# 11_LCD.net
KiCad netlist of a schematic drawn in Altium Designer
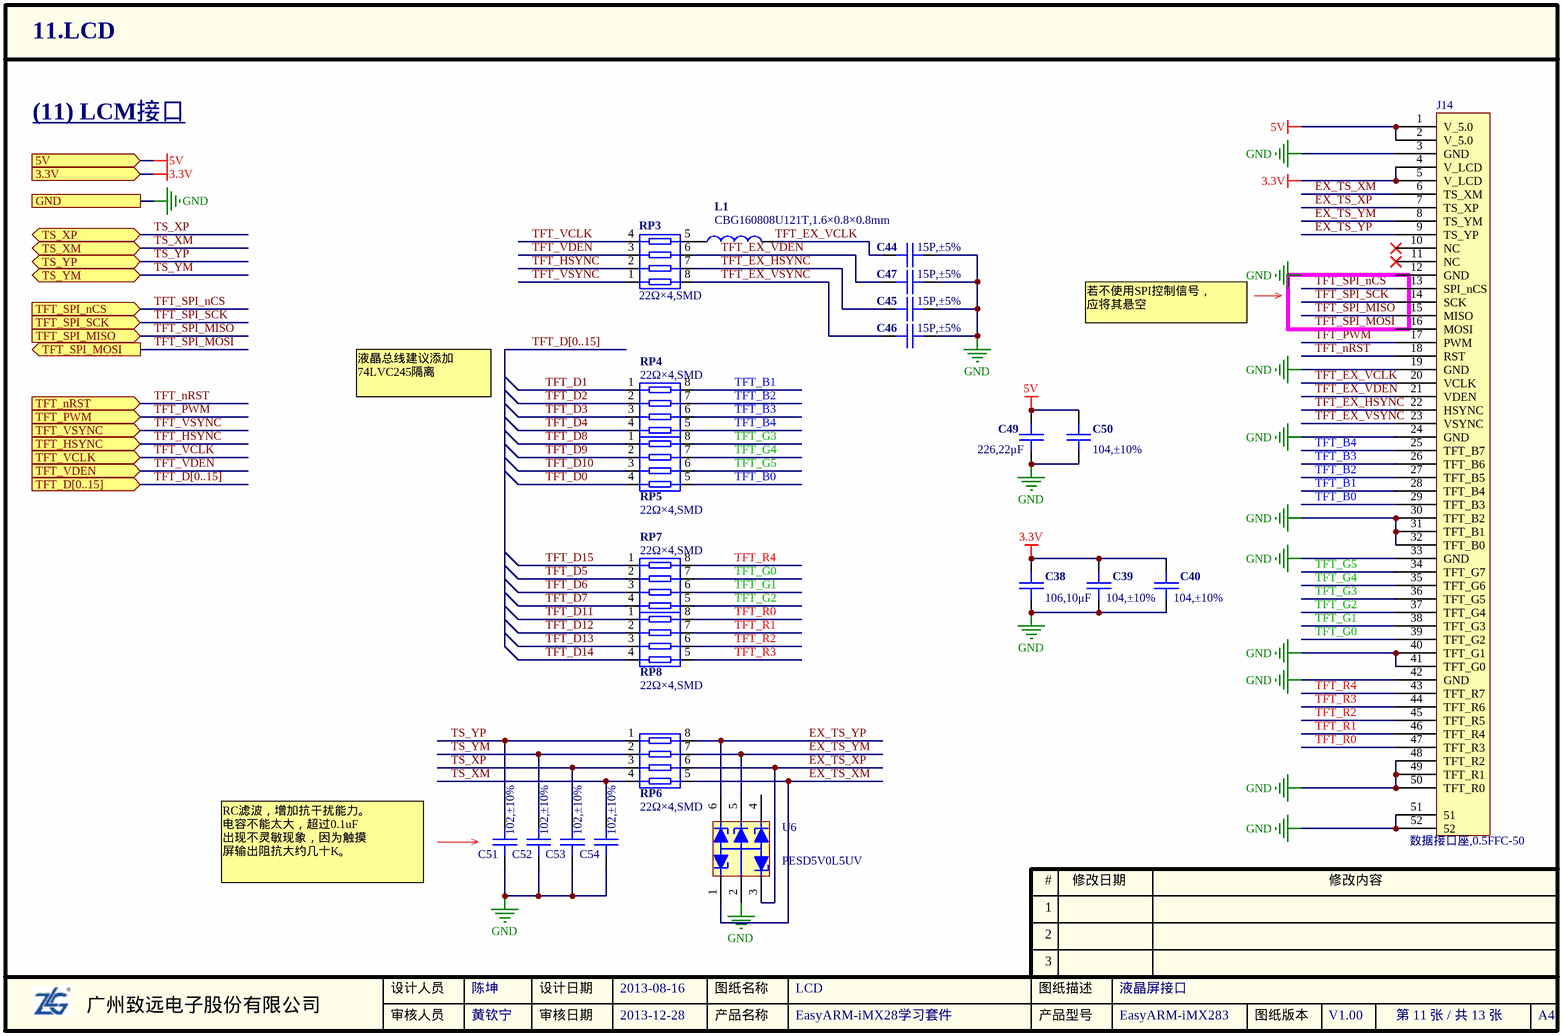
[diagram p0: 11. LCD.SchDoc]

(export (version "E")
  (design (tool "Eeschema 10.0.6"))
  (components
    (comp (ref "C38")
      (value "106,10μF")
      (footprint "0805C")
      (description "106,10μF,±10%,10V,X5R,0805,RoHS")
      (libsource (lib "ErpMaterialData") (part "CAP1"))
    )
    (comp (ref "C39")
      (value "104,±10%")
      (footprint "0603C")
      (description "104,±10%,50V,X7R,0603,*,RoHS")
      (libsource (lib "ErpMaterialData") (part "CAP1"))
    )
    (comp (ref "C40")
      (value "104,±10%")
      (footprint "0603C")
      (description "104,±10%,50V,X7R,0603,*,RoHS")
      (libsource (lib "ErpMaterialData") (part "CAP1"))
    )
    (comp (ref "C44")
      (value "15P,±5%")
      (footprint "0603C")
      (description "15P,±5%,50V,COG,0603,*,RoHS")
      (libsource (lib "ErpMaterialData") (part "CAP1"))
    )
    (comp (ref "C45")
      (value "15P,±5%")
      (footprint "0603C")
      (description "15P,±5%,50V,COG,0603,*,RoHS")
      (libsource (lib "ErpMaterialData") (part "CAP1"))
    )
    (comp (ref "C46")
      (value "15P,±5%")
      (footprint "0603C")
      (description "15P,±5%,50V,COG,0603,*,RoHS")
      (libsource (lib "ErpMaterialData") (part "CAP1"))
    )
    (comp (ref "C47")
      (value "15P,±5%")
      (footprint "0603C")
      (description "15P,±5%,50V,COG,0603,*,RoHS")
      (libsource (lib "ErpMaterialData") (part "CAP1"))
    )
    (comp (ref "C49")
      (value "226,22μF")
      (footprint "0805C")
      (description "226,22μF,±20%,6.3V,X5R,0805,RoHS")
      (libsource (lib "ErpMaterialData") (part "CAP1"))
    )
    (comp (ref "C50")
      (value "104,±10%")
      (footprint "0603C")
      (description "104,±10%,50V,X7R,0603,*,RoHS")
      (libsource (lib "ErpMaterialData") (part "CAP1"))
    )
    (comp (ref "C51")
      (value "102,±10%")
      (footprint "0603C")
      (description "102,±10%,50V,X7R,0603,*,RoHS")
      (libsource (lib "ErpMaterialData") (part "CAP1"))
    )
    (comp (ref "C52")
      (value "102,±10%")
      (footprint "0603C")
      (description "102,±10%,50V,X7R,0603,*,RoHS")
      (libsource (lib "ErpMaterialData") (part "CAP1"))
    )
    (comp (ref "C53")
      (value "102,±10%")
      (footprint "0603C")
      (description "102,±10%,50V,X7R,0603,*,RoHS")
      (libsource (lib "ErpMaterialData") (part "CAP1"))
    )
    (comp (ref "C54")
      (value "102,±10%")
      (footprint "0603C")
      (description "102,±10%,50V,X7R,0603,*,RoHS")
      (libsource (lib "ErpMaterialData") (part "CAP1"))
    )
    (comp (ref "J14")
      (value "数据接口座,0.5FFC-50")
      (footprint "FFC0.5-50P-A")
      (description "数据接口座,0.5FFC-50,SMD,下接,RoHS")
      (fields (field (name "Comment") "FPC-50"))
      (libsource (lib "ErpMaterialData") (part "FPC-50"))
    )
    (comp (ref "L1")
      (value "CBG160808U121T,1.6×0.8×0.8mm")
      (footprint "0603R")
      (description "CBG160808U121T,1.6×0.8×0.8mm,0603,RoHS")
      (fields (field (name "Comment") "INDUCTOR1"))
      (libsource (lib "ErpMaterialData") (part "INDUCTOR1"))
    )
    (comp (ref "RP3")
      (value "22Ω×4,SMD")
      (footprint "0603RA")
      (libsource (lib "ErpMaterialData") (part "RES-P4"))
    )
    (comp (ref "RP4")
      (value "22Ω×4,SMD")
      (footprint "0603RA")
      (libsource (lib "ErpMaterialData") (part "RES-P4"))
    )
    (comp (ref "RP5")
      (value "22Ω×4,SMD")
      (footprint "0603RA")
      (libsource (lib "ErpMaterialData") (part "RES-P4"))
    )
    (comp (ref "RP6")
      (value "22Ω×4,SMD")
      (footprint "0603RA")
      (libsource (lib "ErpMaterialData") (part "RES-P4"))
    )
    (comp (ref "RP7")
      (value "22Ω×4,SMD")
      (footprint "0603RA")
      (libsource (lib "ErpMaterialData") (part "RES-P4"))
    )
    (comp (ref "RP8")
      (value "22Ω×4,SMD")
      (footprint "0603RA")
      (libsource (lib "ErpMaterialData") (part "RES-P4"))
    )
    (comp (ref "U6")
      (value "PESD5V0L5UV")
      (footprint "SOT-666")
      (description "PESD5V0L5UV,SOT-666,NXP,RoHS")
      (libsource (lib "ErpMaterialData") (part "PESD5V0L5UV"))
    )
  )
  (nets
    (net (code "1") (name "/EX_TS_XM") (class "Default")
      (node (ref "J14") (pin "6") (pinfunction "TS_XM_6") (pintype "passive"))
      (node (ref "RP6") (pin "5") (pinfunction "5_5") (pintype "passive"))
      (node (ref "U6") (pin "1") (pintype "passive"))
    )
    (net (code "2") (name "/EX_TS_XP") (class "Default")
      (node (ref "J14") (pin "7") (pinfunction "TS_XP_7") (pintype "passive"))
      (node (ref "RP6") (pin "6") (pinfunction "6_6") (pintype "passive"))
      (node (ref "U6") (pin "3") (pintype "passive"))
    )
    (net (code "3") (name "/EX_TS_YM") (class "Default")
      (node (ref "J14") (pin "8") (pinfunction "TS_YM_8") (pintype "passive"))
      (node (ref "RP6") (pin "7") (pinfunction "7_7") (pintype "passive"))
      (node (ref "U6") (pin "5") (pintype "passive"))
    )
    (net (code "4") (name "/EX_TS_YP") (class "Default")
      (node (ref "J14") (pin "9") (pinfunction "TS_YP_9") (pintype "passive"))
      (node (ref "RP6") (pin "8") (pinfunction "8_8") (pintype "passive"))
      (node (ref "U6") (pin "6") (pintype "passive"))
    )
    (net (code "5") (name "/TFT_B0") (class "Default")
      (node (ref "J14") (pin "29") (pinfunction "TFT_B3_29") (pintype "passive"))
      (node (ref "RP5") (pin "5") (pinfunction "5_5") (pintype "passive"))
    )
    (net (code "6") (name "/TFT_B1") (class "Default")
      (node (ref "J14") (pin "28") (pinfunction "TFT_B4_28") (pintype "passive"))
      (node (ref "RP4") (pin "8") (pinfunction "8_8") (pintype "passive"))
    )
    (net (code "7") (name "/TFT_B2") (class "Default")
      (node (ref "J14") (pin "27") (pinfunction "TFT_B5_27") (pintype "passive"))
      (node (ref "RP4") (pin "7") (pinfunction "7_7") (pintype "passive"))
    )
    (net (code "8") (name "/TFT_B3") (class "Default")
      (node (ref "J14") (pin "26") (pinfunction "TFT_B6_26") (pintype "passive"))
      (node (ref "RP4") (pin "6") (pinfunction "6_6") (pintype "passive"))
    )
    (net (code "9") (name "/TFT_B4") (class "Default")
      (node (ref "J14") (pin "25") (pinfunction "TFT_B7_25") (pintype "passive"))
      (node (ref "RP4") (pin "5") (pinfunction "5_5") (pintype "passive"))
    )
    (net (code "10") (name "/TFT_D0") (class "Default")
      (node (ref "RP5") (pin "4") (pinfunction "4_4") (pintype "passive"))
    )
    (net (code "11") (name "/TFT_D1") (class "Default")
      (node (ref "RP4") (pin "1") (pinfunction "1_1") (pintype "passive"))
    )
    (net (code "12") (name "/TFT_D2") (class "Default")
      (node (ref "RP4") (pin "2") (pinfunction "2_2") (pintype "passive"))
    )
    (net (code "13") (name "/TFT_D3") (class "Default")
      (node (ref "RP4") (pin "3") (pinfunction "3_3") (pintype "passive"))
    )
    (net (code "14") (name "/TFT_D4") (class "Default")
      (node (ref "RP4") (pin "4") (pinfunction "4_4") (pintype "passive"))
    )
    (net (code "15") (name "/TFT_D5") (class "Default")
      (node (ref "RP7") (pin "2") (pinfunction "2_2") (pintype "passive"))
    )
    (net (code "16") (name "/TFT_D6") (class "Default")
      (node (ref "RP7") (pin "3") (pinfunction "3_3") (pintype "passive"))
    )
    (net (code "17") (name "/TFT_D7") (class "Default")
      (node (ref "RP7") (pin "4") (pinfunction "4_4") (pintype "passive"))
    )
    (net (code "18") (name "/TFT_D8") (class "Default")
      (node (ref "RP5") (pin "1") (pinfunction "1_1") (pintype "passive"))
    )
    (net (code "19") (name "/TFT_D9") (class "Default")
      (node (ref "RP5") (pin "2") (pinfunction "2_2") (pintype "passive"))
    )
    (net (code "20") (name "/TFT_D10") (class "Default")
      (node (ref "RP5") (pin "3") (pinfunction "3_3") (pintype "passive"))
    )
    (net (code "21") (name "/TFT_D11") (class "Default")
      (node (ref "RP8") (pin "1") (pinfunction "1_1") (pintype "passive"))
    )
    (net (code "22") (name "/TFT_D12") (class "Default")
      (node (ref "RP8") (pin "2") (pinfunction "2_2") (pintype "passive"))
    )
    (net (code "23") (name "/TFT_D13") (class "Default")
      (node (ref "RP8") (pin "3") (pinfunction "3_3") (pintype "passive"))
    )
    (net (code "24") (name "/TFT_D14") (class "Default")
      (node (ref "RP8") (pin "4") (pinfunction "4_4") (pintype "passive"))
    )
    (net (code "25") (name "/TFT_D15") (class "Default")
      (node (ref "RP7") (pin "1") (pinfunction "1_1") (pintype "passive"))
    )
    (net (code "27") (name "/TFT_EX_HSYNC") (class "Default")
      (node (ref "C45") (pin "1") (pinfunction "1_1") (pintype "passive"))
      (node (ref "J14") (pin "22") (pinfunction "HSYNC_22") (pintype "passive"))
      (node (ref "RP3") (pin "7") (pinfunction "7_7") (pintype "passive"))
    )
    (net (code "28") (name "/TFT_EX_VCLK") (class "Default")
      (node (ref "C44") (pin "1") (pinfunction "1_1") (pintype "passive"))
      (node (ref "J14") (pin "20") (pinfunction "VCLK_20") (pintype "passive"))
      (node (ref "L1") (pin "2") (pinfunction "2_2") (pintype "passive"))
    )
    (net (code "29") (name "/TFT_EX_VDEN") (class "Default")
      (node (ref "C47") (pin "1") (pinfunction "1_1") (pintype "passive"))
      (node (ref "J14") (pin "21") (pinfunction "VDEN_21") (pintype "passive"))
      (node (ref "RP3") (pin "6") (pinfunction "6_6") (pintype "passive"))
    )
    (net (code "30") (name "/TFT_EX_VSYNC") (class "Default")
      (node (ref "C46") (pin "1") (pinfunction "1_1") (pintype "passive"))
      (node (ref "J14") (pin "23") (pinfunction "VSYNC_23") (pintype "passive"))
      (node (ref "RP3") (pin "8") (pinfunction "8_8") (pintype "passive"))
    )
    (net (code "31") (name "/TFT_G0") (class "Default")
      (node (ref "J14") (pin "39") (pinfunction "TFT_G2_39") (pintype "passive"))
      (node (ref "RP7") (pin "7") (pinfunction "7_7") (pintype "passive"))
    )
    (net (code "32") (name "/TFT_G1") (class "Default")
      (node (ref "J14") (pin "38") (pinfunction "TFT_G3_38") (pintype "passive"))
      (node (ref "RP7") (pin "6") (pinfunction "6_6") (pintype "passive"))
    )
    (net (code "33") (name "/TFT_G2") (class "Default")
      (node (ref "J14") (pin "37") (pinfunction "TFT_G4_37") (pintype "passive"))
      (node (ref "RP7") (pin "5") (pinfunction "5_5") (pintype "passive"))
    )
    (net (code "34") (name "/TFT_G3") (class "Default")
      (node (ref "J14") (pin "36") (pinfunction "TFT_G5_36") (pintype "passive"))
      (node (ref "RP5") (pin "8") (pinfunction "8_8") (pintype "passive"))
    )
    (net (code "35") (name "/TFT_G4") (class "Default")
      (node (ref "J14") (pin "35") (pinfunction "TFT_G6_35") (pintype "passive"))
      (node (ref "RP5") (pin "7") (pinfunction "7_7") (pintype "passive"))
    )
    (net (code "36") (name "/TFT_G5") (class "Default")
      (node (ref "J14") (pin "34") (pinfunction "TFT_G7_34") (pintype "passive"))
      (node (ref "RP5") (pin "6") (pinfunction "6_6") (pintype "passive"))
    )
    (net (code "37") (name "/TFT_HSYNC") (class "Default")
      (node (ref "RP3") (pin "2") (pinfunction "2_2") (pintype "passive"))
    )
    (net (code "38") (name "/TFT_PWM") (class "Default")
      (node (ref "J14") (pin "17") (pinfunction "PWM_17") (pintype "passive"))
    )
    (net (code "39") (name "/TFT_R0") (class "Default")
      (node (ref "J14") (pin "47") (pinfunction "TFT_R3_47") (pintype "passive"))
      (node (ref "RP8") (pin "8") (pinfunction "8_8") (pintype "passive"))
    )
    (net (code "40") (name "/TFT_R1") (class "Default")
      (node (ref "J14") (pin "46") (pinfunction "TFT_R4_46") (pintype "passive"))
      (node (ref "RP8") (pin "7") (pinfunction "7_7") (pintype "passive"))
    )
    (net (code "41") (name "/TFT_R2") (class "Default")
      (node (ref "J14") (pin "45") (pinfunction "TFT_R5_45") (pintype "passive"))
      (node (ref "RP8") (pin "6") (pinfunction "6_6") (pintype "passive"))
    )
    (net (code "42") (name "/TFT_R3") (class "Default")
      (node (ref "J14") (pin "44") (pinfunction "TFT_R6_44") (pintype "passive"))
      (node (ref "RP8") (pin "5") (pinfunction "5_5") (pintype "passive"))
    )
    (net (code "43") (name "/TFT_R4") (class "Default")
      (node (ref "J14") (pin "43") (pinfunction "TFT_R7_43") (pintype "passive"))
      (node (ref "RP7") (pin "8") (pinfunction "8_8") (pintype "passive"))
    )
    (net (code "44") (name "/TFT_SPI_MISO") (class "Default")
      (node (ref "J14") (pin "15") (pinfunction "MISO_15") (pintype "passive"))
    )
    (net (code "45") (name "/TFT_SPI_MOSI") (class "Default")
      (node (ref "J14") (pin "16") (pinfunction "MOSI_16") (pintype "passive"))
    )
    (net (code "46") (name "/TFT_SPI_SCK") (class "Default")
      (node (ref "J14") (pin "14") (pinfunction "SCK_14") (pintype "passive"))
    )
    (net (code "47") (name "/TFT_SPI_nCS") (class "Default")
      (node (ref "J14") (pin "13") (pinfunction "SPI_nCS_13") (pintype "passive"))
    )
    (net (code "48") (name "/TFT_VCLK") (class "Default")
      (node (ref "RP3") (pin "4") (pinfunction "4_4") (pintype "passive"))
    )
    (net (code "49") (name "/TFT_VDEN") (class "Default")
      (node (ref "RP3") (pin "3") (pinfunction "3_3") (pintype "passive"))
    )
    (net (code "50") (name "/TFT_VSYNC") (class "Default")
      (node (ref "RP3") (pin "1") (pinfunction "1_1") (pintype "passive"))
    )
    (net (code "51") (name "/TFT_nRST") (class "Default")
      (node (ref "J14") (pin "18") (pinfunction "RST_18") (pintype "passive"))
    )
    (net (code "52") (name "/TS_XM") (class "Default")
      (node (ref "C54") (pin "1") (pinfunction "1_1") (pintype "passive"))
      (node (ref "RP6") (pin "4") (pinfunction "4_4") (pintype "passive"))
    )
    (net (code "53") (name "/TS_XP") (class "Default")
      (node (ref "C53") (pin "1") (pinfunction "1_1") (pintype "passive"))
      (node (ref "RP6") (pin "3") (pinfunction "3_3") (pintype "passive"))
    )
    (net (code "54") (name "/TS_YM") (class "Default")
      (node (ref "C52") (pin "1") (pinfunction "1_1") (pintype "passive"))
      (node (ref "RP6") (pin "2") (pinfunction "2_2") (pintype "passive"))
    )
    (net (code "55") (name "/TS_YP") (class "Default")
      (node (ref "C51") (pin "1") (pinfunction "1_1") (pintype "passive"))
      (node (ref "RP6") (pin "1") (pinfunction "1_1") (pintype "passive"))
    )
    (net (code "56") (name "3.3V") (class "Default")
      (node (ref "C38") (pin "1") (pinfunction "1_1") (pintype "passive"))
      (node (ref "C39") (pin "1") (pinfunction "1_1") (pintype "passive"))
      (node (ref "C40") (pin "1") (pinfunction "1_1") (pintype "passive"))
      (node (ref "J14") (pin "4") (pinfunction "V_LCD_4") (pintype "passive"))
      (node (ref "J14") (pin "5") (pinfunction "V_LCD_5") (pintype "passive"))
    )
    (net (code "57") (name "5V") (class "Default")
      (node (ref "C49") (pin "1") (pinfunction "1_1") (pintype "passive"))
      (node (ref "C50") (pin "1") (pinfunction "1_1") (pintype "passive"))
      (node (ref "J14") (pin "1") (pinfunction "V_5.0_1") (pintype "passive"))
      (node (ref "J14") (pin "2") (pinfunction "V_5.0_2") (pintype "passive"))
    )
    (net (code "58") (name "GND") (class "Default")
      (node (ref "C38") (pin "2") (pinfunction "2_2") (pintype "passive"))
      (node (ref "C39") (pin "2") (pinfunction "2_2") (pintype "passive"))
      (node (ref "C40") (pin "2") (pinfunction "2_2") (pintype "passive"))
      (node (ref "C44") (pin "2") (pinfunction "2_2") (pintype "passive"))
      (node (ref "C45") (pin "2") (pinfunction "2_2") (pintype "passive"))
      (node (ref "C46") (pin "2") (pinfunction "2_2") (pintype "passive"))
      (node (ref "C47") (pin "2") (pinfunction "2_2") (pintype "passive"))
      (node (ref "C49") (pin "2") (pinfunction "2_2") (pintype "passive"))
      (node (ref "C50") (pin "2") (pinfunction "2_2") (pintype "passive"))
      (node (ref "C51") (pin "2") (pinfunction "2_2") (pintype "passive"))
      (node (ref "C52") (pin "2") (pinfunction "2_2") (pintype "passive"))
      (node (ref "C53") (pin "2") (pinfunction "2_2") (pintype "passive"))
      (node (ref "C54") (pin "2") (pinfunction "2_2") (pintype "passive"))
      (node (ref "J14") (pin "12") (pinfunction "GND_12") (pintype "passive"))
      (node (ref "J14") (pin "19") (pinfunction "GND_19") (pintype "passive"))
      (node (ref "J14") (pin "24") (pinfunction "GND_24") (pintype "passive"))
      (node (ref "J14") (pin "3") (pinfunction "GND_3") (pintype "passive"))
      (node (ref "J14") (pin "30") (pinfunction "TFT_B2_30") (pintype "passive"))
      (node (ref "J14") (pin "31") (pinfunction "TFT_B1_31") (pintype "passive"))
      (node (ref "J14") (pin "32") (pinfunction "TFT_B0_32") (pintype "passive"))
      (node (ref "J14") (pin "33") (pinfunction "GND_33") (pintype "passive"))
      (node (ref "J14") (pin "40") (pinfunction "TFT_G1_40") (pintype "passive"))
      (node (ref "J14") (pin "41") (pinfunction "TFT_G0_41") (pintype "passive"))
      (node (ref "J14") (pin "42") (pinfunction "GND_42") (pintype "passive"))
      (node (ref "J14") (pin "48") (pinfunction "TFT_R2_48") (pintype "passive"))
      (node (ref "J14") (pin "49") (pinfunction "TFT_R1_49") (pintype "passive"))
      (node (ref "J14") (pin "50") (pinfunction "TFT_R0_50") (pintype "passive"))
      (node (ref "J14") (pin "51") (pinfunction "51_51") (pintype "passive"))
      (node (ref "J14") (pin "52") (pinfunction "52_52") (pintype "passive"))
      (node (ref "U6") (pin "2") (pintype "passive"))
    )
    (net (code "59") (name "Net-(L1-Pad1)") (class "Default")
      (node (ref "L1") (pin "1") (pinfunction "1_1") (pintype "passive"))
      (node (ref "RP3") (pin "5") (pinfunction "5_5") (pintype "passive"))
    )
    (net (code "60") (name "unconnected-(J14-NC-Pad10)") (class "Default")
      (node (ref "J14") (pin "10") (pinfunction "NC_10") (pintype "passive+no_connect"))
    )
    (net (code "61") (name "unconnected-(J14-NC-Pad11)") (class "Default")
      (node (ref "J14") (pin "11") (pinfunction "NC_11") (pintype "passive+no_connect"))
    )
    (net (code "62") (name "unconnected-(U6-Pad4)") (class "Default")
      (node (ref "U6") (pin "4") (pintype "passive"))
    )
  )
)
